# ESP32_with_USBC.net
KiCad netlist of a schematic drawn in Altium Designer
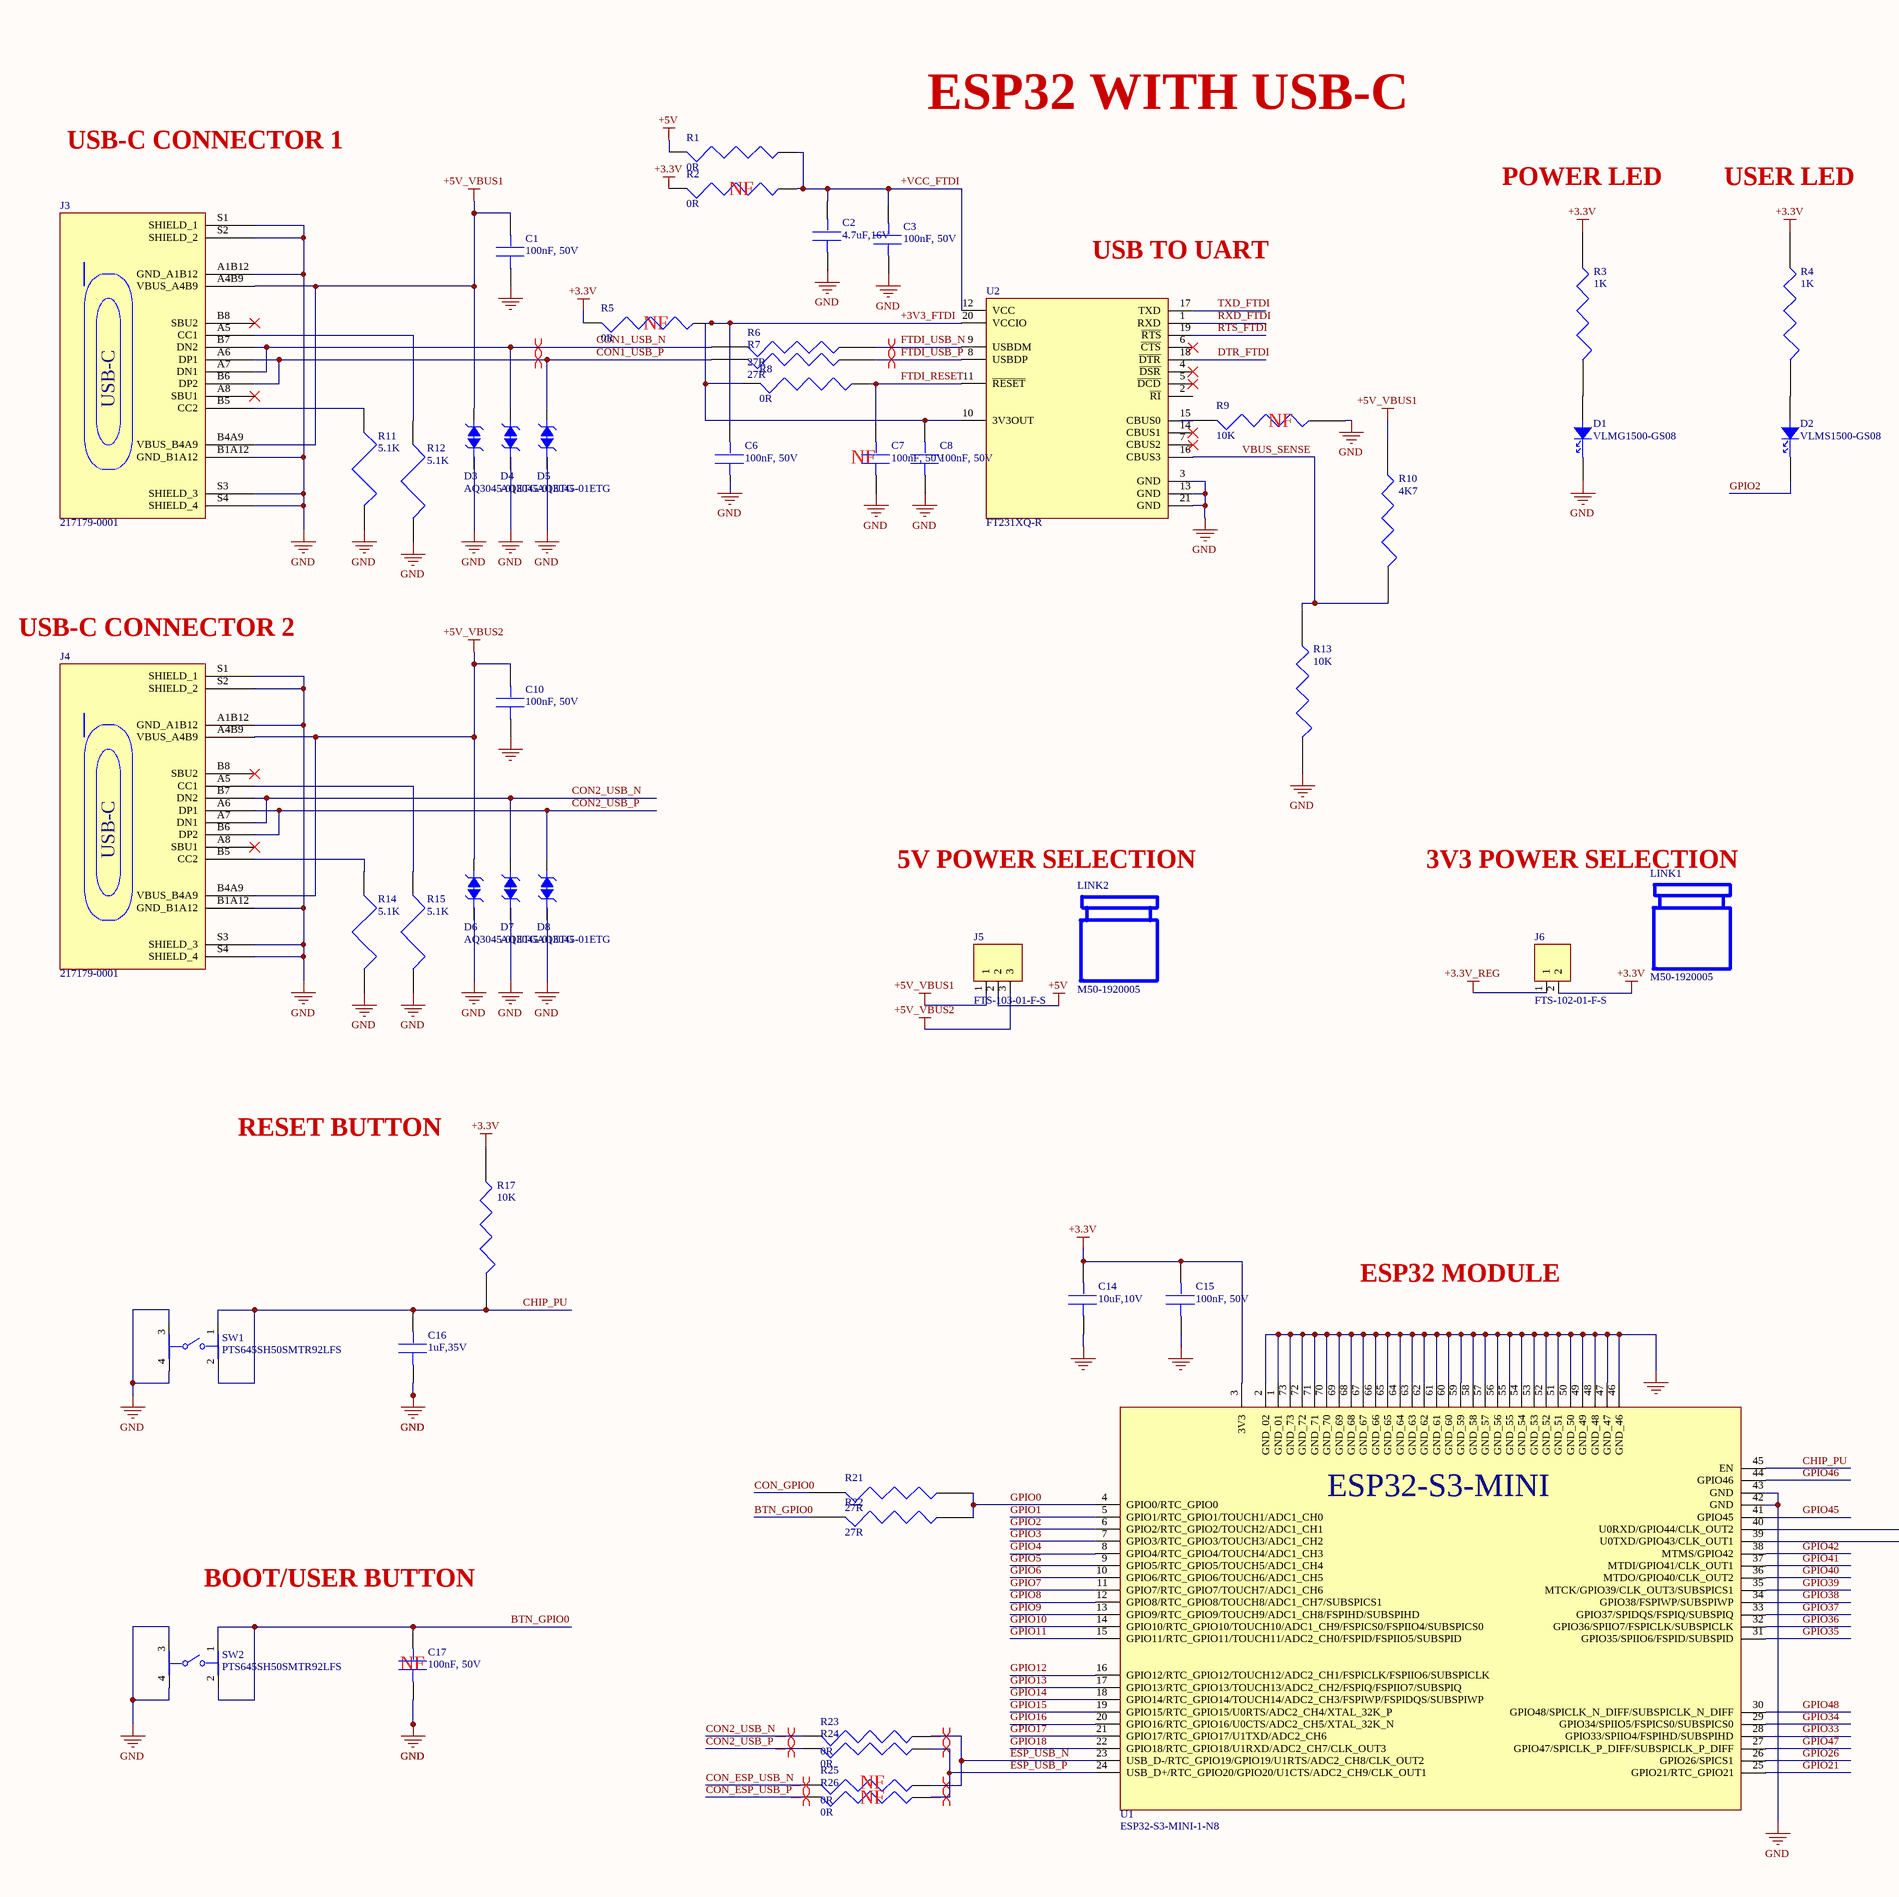
[diagram p0: ESP32 with USBC.SchDoc, left]
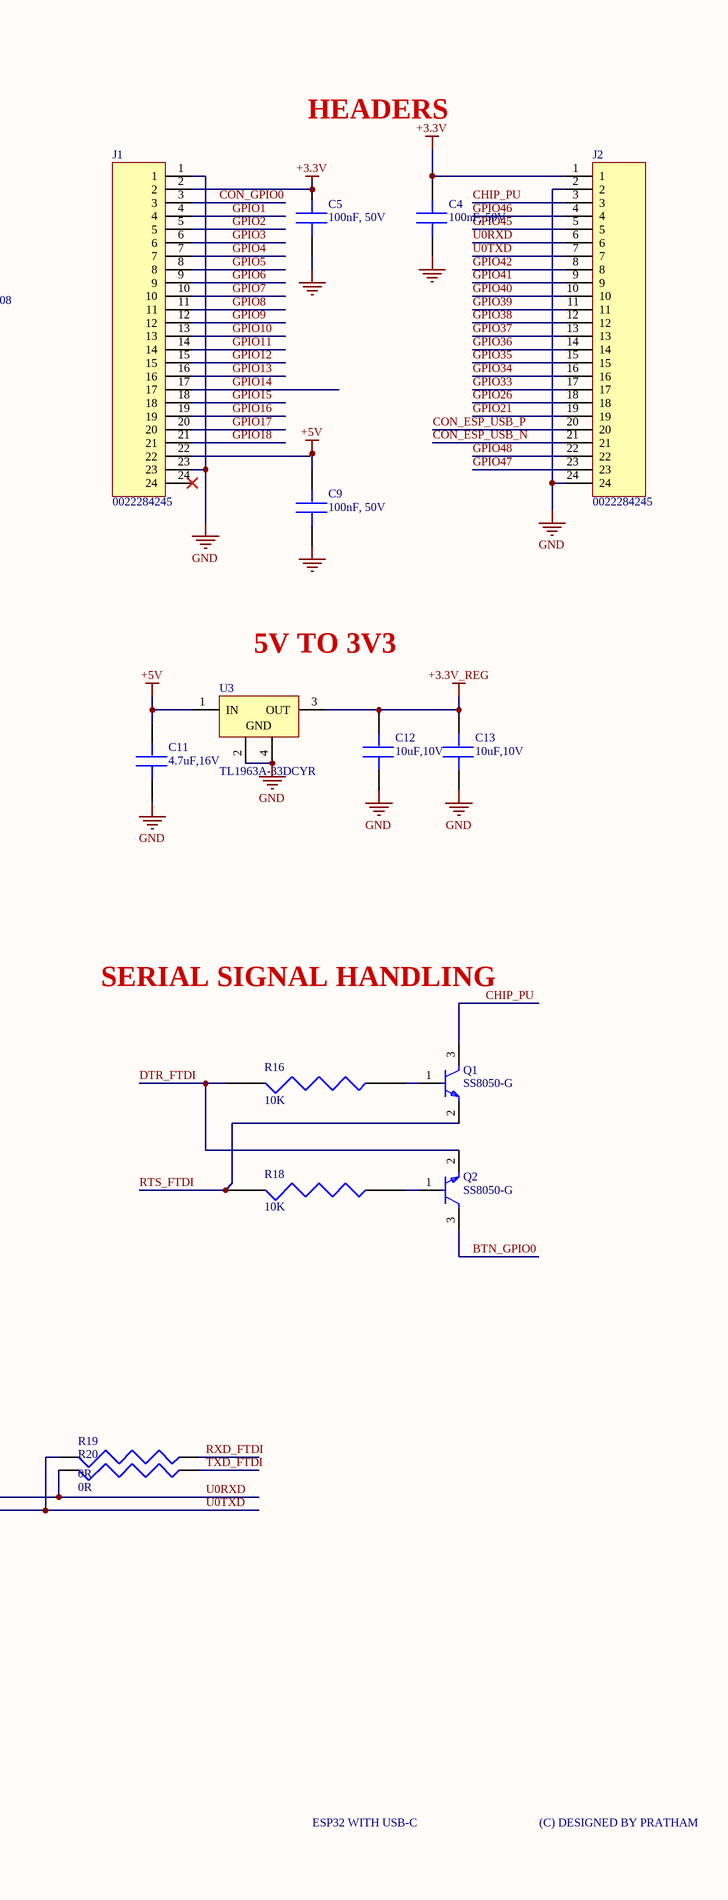
[diagram p1: ESP32 with USBC.SchDoc, right]

(export (version "E")
  (design (tool "Eeschema 10.0.6"))
  (components
    (comp (ref "C1")
      (value "100nF, 50V")
      (footprint "CAPC1005X55N")
      (description "CAP CER 0.1UF 50V X7R 0402")
      (fields (field (name "LCSC PART NUMBER") "C307331"))
      (libsource (lib "Schlib1") (part "CL05B104KB54PNC"))
    )
    (comp (ref "C2")
      (value "4.7uF,16V")
      (footprint "CAPC1005X55N")
      (description "CAP CER 4.7UF 16V X5R 0402")
      (fields
        (field (name "MANUFACTURER") "Samsung Electro-Mechanics")
        (field (name "MANUFACTURER PART NUMBER") "CL05A475MO5NUNC")
      )
      (libsource (lib "Schlib1") (part "CL05A475MO5NUNC"))
    )
    (comp (ref "C3")
      (value "100nF, 50V")
      (footprint "CAPC1005X55N")
      (description "CAP CER 0.1UF 50V X7R 0402")
      (fields (field (name "LCSC PART NUMBER") "C307331"))
      (libsource (lib "Schlib1") (part "CL05B104KB54PNC"))
    )
    (comp (ref "C4")
      (value "100nF, 50V")
      (footprint "CAPC1005X55N")
      (description "CAP CER 0.1UF 50V X7R 0402")
      (fields (field (name "LCSC PART NUMBER") "C307331"))
      (libsource (lib "Schlib1") (part "CL05B104KB54PNC"))
    )
    (comp (ref "C5")
      (value "100nF, 50V")
      (footprint "CAPC1005X55N")
      (description "CAP CER 0.1UF 50V X7R 0402")
      (fields (field (name "LCSC PART NUMBER") "C307331"))
      (libsource (lib "Schlib1") (part "CL05B104KB54PNC"))
    )
    (comp (ref "C6")
      (value "100nF, 50V")
      (footprint "CAPC1005X55N")
      (description "CAP CER 0.1UF 50V X7R 0402")
      (fields (field (name "LCSC PART NUMBER") "C307331"))
      (libsource (lib "Schlib1") (part "CL05B104KB54PNC"))
    )
    (comp (ref "C7")
      (value "100nF, 50V")
      (footprint "CAPC1005X55N")
      (description "CAP CER 0.1UF 50V X7R 0402")
      (fields (field (name "LCSC PART NUMBER") "C307331"))
      (libsource (lib "Schlib1") (part "CL05B104KB54PNC"))
    )
    (comp (ref "C8")
      (value "100nF, 50V")
      (footprint "CAPC1005X55N")
      (description "CAP CER 0.1UF 50V X7R 0402")
      (fields (field (name "LCSC PART NUMBER") "C307331"))
      (libsource (lib "Schlib1") (part "CL05B104KB54PNC"))
    )
    (comp (ref "C9")
      (value "100nF, 50V")
      (footprint "CAPC1005X55N")
      (description "CAP CER 0.1UF 50V X7R 0402")
      (fields (field (name "LCSC PART NUMBER") "C307331"))
      (libsource (lib "Schlib1") (part "CL05B104KB54PNC"))
    )
    (comp (ref "C10")
      (value "100nF, 50V")
      (footprint "CAPC1005X55N")
      (description "CAP CER 0.1UF 50V X7R 0402")
      (fields (field (name "LCSC PART NUMBER") "C307331"))
      (libsource (lib "Schlib1") (part "CL05B104KB54PNC"))
    )
    (comp (ref "C11")
      (value "4.7uF,16V")
      (footprint "CAPC1005X55N")
      (description "CAP CER 4.7UF 16V X5R 0402")
      (fields
        (field (name "MANUFACTURER") "Samsung Electro-Mechanics")
        (field (name "MANUFACTURER PART NUMBER") "CL05A475MO5NUNC")
      )
      (libsource (lib "Schlib1") (part "CL05A475MO5NUNC"))
    )
    (comp (ref "C12")
      (value "10uF,10V")
      (footprint "CAPC1005X55N")
      (description "CAP CER 10UF 10V X5R 0402")
      (fields
        (field (name "MANUFACTURER") "Samsung Electro-Mechanics")
        (field (name "MANUFACTURER PART NUMBER") "CL05A106MP8NUB8")
      )
      (libsource (lib "Schlib1") (part "CL05A106MP8NUB8"))
    )
    (comp (ref "C13")
      (value "10uF,10V")
      (footprint "CAPC1005X55N")
      (description "CAP CER 10UF 10V X5R 0402")
      (fields
        (field (name "MANUFACTURER") "Samsung Electro-Mechanics")
        (field (name "MANUFACTURER PART NUMBER") "CL05A106MP8NUB8")
      )
      (libsource (lib "Schlib1") (part "CL05A106MP8NUB8"))
    )
    (comp (ref "C14")
      (value "10uF,10V")
      (footprint "CAPC1005X55N")
      (description "CAP CER 10UF 10V X5R 0402")
      (fields
        (field (name "MANUFACTURER") "Samsung Electro-Mechanics")
        (field (name "MANUFACTURER PART NUMBER") "CL05A106MP8NUB8")
      )
      (libsource (lib "Schlib1") (part "CL05A106MP8NUB8"))
    )
    (comp (ref "C15")
      (value "100nF, 50V")
      (footprint "CAPC1005X55N")
      (description "CAP CER 0.1UF 50V X7R 0402")
      (fields (field (name "LCSC PART NUMBER") "C307331"))
      (libsource (lib "Schlib1") (part "CL05B104KB54PNC"))
    )
    (comp (ref "C16")
      (value "1uF,35V")
      (footprint "CAPC1005X55N")
      (description "CAP CER 1UF 35V X5R 0402")
      (fields
        (field (name "MANUFACTURER") "Samsung Electro-Mechanics")
        (field (name "MANUFACTURER PART NUMBER") "CL05A105KL5NRNC")
      )
      (libsource (lib "Schlib1") (part "CL05A105KL5NRNC"))
    )
    (comp (ref "C17")
      (value "100nF, 50V")
      (footprint "CAPC1005X55N")
      (description "CAP CER 0.1UF 50V X7R 0402")
      (fields (field (name "LCSC PART NUMBER") "C307331"))
      (libsource (lib "Schlib1") (part "CL05B104KB54PNC"))
    )
    (comp (ref "D1")
      (value "VLMG1500-GS08")
      (footprint "LED0402G")
      (description "LED YLW-GRN 0402 SMD")
      (fields (field (name "MANUFACTURER") "Vishay") (field (name "LCSC PART NUMBER") "C511404"))
      (libsource (lib "Schlib1") (part "VLMG1500-GS08"))
    )
    (comp (ref "D2")
      (value "VLMS1500-GS08")
      (footprint "LED0402R")
      (description "LED RED 0402 SMD")
      (fields (field (name "MANUFACTURER") "Vishay") (field (name "LCSC PART NUMBER") "C511370"))
      (libsource (lib "Schlib1") (part "VLMS1500-GS08"))
    )
    (comp (ref "D3")
      (value "AQ3045-01ETG")
      (footprint "S0D882")
      (description "TVS DIODE 5.3VWM 12VC SOD882")
      (fields (field (name "MANUFACTURER") "Littelfuse") (field (name "LCSC PART NUMBER") "C3710326"))
      (libsource (lib "Schlib1") (part "AQ3045-01ETG"))
    )
    (comp (ref "D4")
      (value "AQ3045-01ETG")
      (footprint "S0D882")
      (description "TVS DIODE 5.3VWM 12VC SOD882")
      (fields (field (name "MANUFACTURER") "Littelfuse") (field (name "LCSC PART NUMBER") "C3710326"))
      (libsource (lib "Schlib1") (part "AQ3045-01ETG"))
    )
    (comp (ref "D5")
      (value "AQ3045-01ETG")
      (footprint "S0D882")
      (description "TVS DIODE 5.3VWM 12VC SOD882")
      (fields (field (name "MANUFACTURER") "Littelfuse") (field (name "LCSC PART NUMBER") "C3710326"))
      (libsource (lib "Schlib1") (part "AQ3045-01ETG"))
    )
    (comp (ref "D6")
      (value "AQ3045-01ETG")
      (footprint "S0D882")
      (description "TVS DIODE 5.3VWM 12VC SOD882")
      (fields (field (name "MANUFACTURER") "Littelfuse") (field (name "LCSC PART NUMBER") "C3710326"))
      (libsource (lib "Schlib1") (part "AQ3045-01ETG"))
    )
    (comp (ref "D7")
      (value "AQ3045-01ETG")
      (footprint "S0D882")
      (description "TVS DIODE 5.3VWM 12VC SOD882")
      (fields (field (name "MANUFACTURER") "Littelfuse") (field (name "LCSC PART NUMBER") "C3710326"))
      (libsource (lib "Schlib1") (part "AQ3045-01ETG"))
    )
    (comp (ref "D8")
      (value "AQ3045-01ETG")
      (footprint "S0D882")
      (description "TVS DIODE 5.3VWM 12VC SOD882")
      (fields (field (name "MANUFACTURER") "Littelfuse") (field (name "LCSC PART NUMBER") "C3710326"))
      (libsource (lib "Schlib1") (part "AQ3045-01ETG"))
    )
    (comp (ref "J1")
      (value "0022284245")
      (footprint "HDR_1X24_2.54MM")
      (description "CONN HEADER VERT 24POS 2.54MM")
      (fields (field (name "MANUFACTURER") "Molex") (field (name "MANUFACTURER PART NUMBER") "22-28-4245"))
      (libsource (lib "Schlib1") (part "0022284245"))
    )
    (comp (ref "J2")
      (value "0022284245")
      (footprint "HDR_1X24_2.54MM")
      (description "CONN HEADER VERT 24POS 2.54MM")
      (fields (field (name "MANUFACTURER") "Molex") (field (name "MANUFACTURER PART NUMBER") "22-28-4245"))
      (libsource (lib "") (part "0022284245_1"))
    )
    (comp (ref "J3")
      (value "217179-0001")
      (footprint "FP-2171790001-MFG")
      (description "CONN RCP USB2.0 TYP C 24P SMD RA")
      (fields (field (name "MANUFACTURER") "Molex") (field (name "LCSC PART NUMBER") "C3197684"))
      (libsource (lib "Schlib1") (part "217179-0001"))
    )
    (comp (ref "J4")
      (value "217179-0001")
      (footprint "FP-2171790001-MFG")
      (description "CONN RCP USB2.0 TYP C 24P SMD RA")
      (fields (field (name "MANUFACTURER") "Molex") (field (name "LCSC PART NUMBER") "C3197684"))
      (libsource (lib "Schlib1") (part "217179-0001"))
    )
    (comp (ref "J5")
      (value "FTS-103-01-F-S")
      (footprint "HDR_1X3_27MM")
      (description "CONN HEADER VERT 3POS 1.27MM")
      (fields (field (name "MANUFACTURER") "Samtec") (field (name "LCSC PART NUMBER") "C3333578"))
      (libsource (lib "Schlib1") (part "FTS-103-01-F-S"))
    )
    (comp (ref "J6")
      (value "FTS-102-01-F-S")
      (footprint "HDR_1X2_1.27MM")
      (description "CONN HEADER VERT 2POS 1.27MM")
      (fields (field (name "MANUFACTURER") "Samtec") (field (name "LCSC PART NUMBER") "C6045317"))
      (libsource (lib "Schlib1") (part "FTS-102-01-F-S"))
    )
    (comp (ref "LINK1")
      (value "M50-1920005")
      (description "CONN SHUNT 1.27MM RED")
      (fields (field (name "MANUFACTURER") "Harwin") (field (name "LCSC PART NUMBER") "C6985646"))
      (libsource (lib "Schlib1") (part "M50-1920005"))
    )
    (comp (ref "LINK2")
      (value "M50-1920005")
      (description "CONN SHUNT 1.27MM RED")
      (fields (field (name "MANUFACTURER") "Harwin") (field (name "LCSC PART NUMBER") "C6985646"))
      (libsource (lib "Schlib1") (part "M50-1920005"))
    )
    (comp (ref "Q1")
      (value "SS8050-G")
      (footprint "FP-SS8050-G-IPC_B")
      (description "TRANS NPN 25V 1.5A SOT-23-3")
      (fields (field (name "MANUFACTURER") "Comchip") (field (name "LCSC PART NUMBER") "C3199946"))
      (libsource (lib "Schlib1") (part "SS8050-G"))
    )
    (comp (ref "Q2")
      (value "SS8050-G")
      (footprint "FP-SS8050-G-IPC_B")
      (description "TRANS NPN 25V 1.5A SOT-23-3")
      (fields (field (name "MANUFACTURER") "Comchip") (field (name "LCSC PART NUMBER") "C3199946"))
      (libsource (lib "Schlib1") (part "SS8050-G"))
    )
    (comp (ref "R1")
      (value "0R")
      (footprint "RESC1005X37N")
      (description "RES 0 OHM JUMPER 1/16W 0402")
      (fields
        (field (name "MANUFACTURER") "Yageo Group")
        (field (name "MANUFACTURER PART NUMBER") "RC0402JR-070RL")
      )
      (libsource (lib "Schlib1") (part "RC0402JR-070RL"))
    )
    (comp (ref "R2")
      (value "0R")
      (footprint "RESC1005X37N")
      (description "RES 0 OHM JUMPER 1/16W 0402")
      (fields
        (field (name "MANUFACTURER") "Yageo Group")
        (field (name "MANUFACTURER PART NUMBER") "RC0402JR-070RL")
      )
      (libsource (lib "Schlib1") (part "RC0402JR-070RL"))
    )
    (comp (ref "R3")
      (value "1K")
      (footprint "RESC1005X37N")
      (description "RES 1K OHM 1% 1/16W 0402")
      (fields
        (field (name "MANUFACTURER") "Yageo Group")
        (field (name "MANUFACTURER PART NUMBER") "RC0402FR-071KL")
      )
      (libsource (lib "Schlib1") (part "RC0402FR-071KL"))
    )
    (comp (ref "R4")
      (value "1K")
      (footprint "RESC1005X37N")
      (description "RES 1K OHM 1% 1/16W 0402")
      (fields
        (field (name "MANUFACTURER") "Yageo Group")
        (field (name "MANUFACTURER PART NUMBER") "RC0402FR-071KL")
      )
      (libsource (lib "Schlib1") (part "RC0402FR-071KL"))
    )
    (comp (ref "R5")
      (value "0R")
      (footprint "RESC1005X37N")
      (description "RES 0 OHM JUMPER 1/16W 0402")
      (fields
        (field (name "MANUFACTURER") "Yageo Group")
        (field (name "MANUFACTURER PART NUMBER") "RC0402JR-070RL")
      )
      (libsource (lib "Schlib1") (part "RC0402JR-070RL"))
    )
    (comp (ref "R6")
      (value "27R")
      (footprint "RESC1005X37N")
      (description "RES 27 OHM 1% 1/16W 0402")
      (fields
        (field (name "MANUFACTURER") "Yageo Group")
        (field (name "MANUFACTURER PART NUMBER") "RC0402FR-0727RL")
      )
      (libsource (lib "Schlib1") (part "RC0402FR-0727RL"))
    )
    (comp (ref "R7")
      (value "27R")
      (footprint "RESC1005X37N")
      (description "RES 27 OHM 1% 1/16W 0402")
      (fields
        (field (name "MANUFACTURER") "Yageo Group")
        (field (name "MANUFACTURER PART NUMBER") "RC0402FR-0727RL")
      )
      (libsource (lib "Schlib1") (part "RC0402FR-0727RL"))
    )
    (comp (ref "R8")
      (value "0R")
      (footprint "RESC1005X37N")
      (description "RES 0 OHM JUMPER 1/16W 0402")
      (fields
        (field (name "MANUFACTURER") "Yageo Group")
        (field (name "MANUFACTURER PART NUMBER") "RC0402JR-070RL")
      )
      (libsource (lib "Schlib1") (part "RC0402JR-070RL"))
    )
    (comp (ref "R9")
      (value "10K")
      (footprint "RESC1005X37N")
      (description "RES SMD 10K OHM 1% 1/16W 0402")
      (fields
        (field (name "MANUFACTURER") "Yageo Group")
        (field (name "MANUFACTURER PART NUMBER") "AC0402FR-0710KL")
      )
      (libsource (lib "Schlib1") (part "AC0402FR-0710KL"))
    )
    (comp (ref "R10")
      (value "4K7")
      (footprint "RESC1005X37N")
      (description "RES 4.7K OHM 1% 1/16W 0402")
      (fields
        (field (name "MANUFACTURER") "Yageo Group")
        (field (name "MANUFACTURER PART NUMBER") "RC0402FR-074K7L")
      )
      (libsource (lib "Schlib1") (part "RC0402FR-074K7L"))
    )
    (comp (ref "R11")
      (value "5.1K")
      (footprint "RESC1005X37N")
      (description "RES 5.1K OHM 1% 1/8W 0402")
      (fields
        (field (name "MANUFACTURER") "Yageo Group")
        (field (name "MANUFACTURER PART NUMBER") "AC0402FR-7W5K1L")
      )
      (libsource (lib "Schlib1") (part "AC0402FR-7W5K1L"))
    )
    (comp (ref "R12")
      (value "5.1K")
      (footprint "RESC1005X37N")
      (description "RES 5.1K OHM 1% 1/8W 0402")
      (fields
        (field (name "MANUFACTURER") "Yageo Group")
        (field (name "MANUFACTURER PART NUMBER") "AC0402FR-7W5K1L")
      )
      (libsource (lib "Schlib1") (part "AC0402FR-7W5K1L"))
    )
    (comp (ref "R13")
      (value "10K")
      (footprint "RESC1005X37N")
      (description "RES SMD 10K OHM 1% 1/16W 0402")
      (fields
        (field (name "MANUFACTURER") "Yageo Group")
        (field (name "MANUFACTURER PART NUMBER") "AC0402FR-0710KL")
      )
      (libsource (lib "Schlib1") (part "AC0402FR-0710KL"))
    )
    (comp (ref "R14")
      (value "5.1K")
      (footprint "RESC1005X37N")
      (description "RES 5.1K OHM 1% 1/8W 0402")
      (fields
        (field (name "MANUFACTURER") "Yageo Group")
        (field (name "MANUFACTURER PART NUMBER") "AC0402FR-7W5K1L")
      )
      (libsource (lib "Schlib1") (part "AC0402FR-7W5K1L"))
    )
    (comp (ref "R15")
      (value "5.1K")
      (footprint "RESC1005X37N")
      (description "RES 5.1K OHM 1% 1/8W 0402")
      (fields
        (field (name "MANUFACTURER") "Yageo Group")
        (field (name "MANUFACTURER PART NUMBER") "AC0402FR-7W5K1L")
      )
      (libsource (lib "Schlib1") (part "AC0402FR-7W5K1L"))
    )
    (comp (ref "R16")
      (value "10K")
      (footprint "RESC1005X37N")
      (description "RES SMD 10K OHM 1% 1/16W 0402")
      (fields
        (field (name "MANUFACTURER") "Yageo Group")
        (field (name "MANUFACTURER PART NUMBER") "AC0402FR-0710KL")
      )
      (libsource (lib "Schlib1") (part "AC0402FR-0710KL"))
    )
    (comp (ref "R17")
      (value "10K")
      (footprint "RESC1005X37N")
      (description "RES SMD 10K OHM 1% 1/16W 0402")
      (fields
        (field (name "MANUFACTURER") "Yageo Group")
        (field (name "MANUFACTURER PART NUMBER") "AC0402FR-0710KL")
      )
      (libsource (lib "") (part "AC0402FR-0710KL_1"))
    )
    (comp (ref "R18")
      (value "10K")
      (footprint "RESC1005X37N")
      (description "RES SMD 10K OHM 1% 1/16W 0402")
      (fields
        (field (name "MANUFACTURER") "Yageo Group")
        (field (name "MANUFACTURER PART NUMBER") "AC0402FR-0710KL")
      )
      (libsource (lib "") (part "AC0402FR-0710KL_1"))
    )
    (comp (ref "R19")
      (value "0R")
      (footprint "RESC1005X37N")
      (description "RES 0 OHM JUMPER 1/16W 0402")
      (fields
        (field (name "MANUFACTURER") "Yageo Group")
        (field (name "MANUFACTURER PART NUMBER") "RC0402JR-070RL")
      )
      (libsource (lib "Schlib1") (part "RC0402JR-070RL"))
    )
    (comp (ref "R20")
      (value "0R")
      (footprint "RESC1005X37N")
      (description "RES 0 OHM JUMPER 1/16W 0402")
      (fields
        (field (name "MANUFACTURER") "Yageo Group")
        (field (name "MANUFACTURER PART NUMBER") "RC0402JR-070RL")
      )
      (libsource (lib "Schlib1") (part "RC0402JR-070RL"))
    )
    (comp (ref "R21")
      (value "27R")
      (footprint "RESC1005X37N")
      (description "RES 27 OHM 1% 1/16W 0402")
      (fields
        (field (name "MANUFACTURER") "Yageo Group")
        (field (name "MANUFACTURER PART NUMBER") "RC0402FR-0727RL")
      )
      (libsource (lib "Schlib1") (part "RC0402FR-0727RL"))
    )
    (comp (ref "R22")
      (value "27R")
      (footprint "RESC1005X37N")
      (description "RES 27 OHM 1% 1/16W 0402")
      (fields
        (field (name "MANUFACTURER") "Yageo Group")
        (field (name "MANUFACTURER PART NUMBER") "RC0402FR-0727RL")
      )
      (libsource (lib "Schlib1") (part "RC0402FR-0727RL"))
    )
    (comp (ref "R23")
      (value "0R")
      (footprint "RESC1005X37N")
      (description "RES 0 OHM JUMPER 1/16W 0402")
      (fields
        (field (name "MANUFACTURER") "Yageo Group")
        (field (name "MANUFACTURER PART NUMBER") "RC0402JR-070RL")
      )
      (libsource (lib "Schlib1") (part "RC0402JR-070RL"))
    )
    (comp (ref "R24")
      (value "0R")
      (footprint "RESC1005X37N")
      (description "RES 0 OHM JUMPER 1/16W 0402")
      (fields
        (field (name "MANUFACTURER") "Yageo Group")
        (field (name "MANUFACTURER PART NUMBER") "RC0402JR-070RL")
      )
      (libsource (lib "Schlib1") (part "RC0402JR-070RL"))
    )
    (comp (ref "R25")
      (value "0R")
      (footprint "RESC1005X37N")
      (description "RES 0 OHM JUMPER 1/16W 0402")
      (fields
        (field (name "MANUFACTURER") "Yageo Group")
        (field (name "MANUFACTURER PART NUMBER") "RC0402JR-070RL")
      )
      (libsource (lib "Schlib1") (part "RC0402JR-070RL"))
    )
    (comp (ref "R26")
      (value "0R")
      (footprint "RESC1005X37N")
      (description "RES 0 OHM JUMPER 1/16W 0402")
      (fields
        (field (name "MANUFACTURER") "Yageo Group")
        (field (name "MANUFACTURER PART NUMBER") "RC0402JR-070RL")
      )
      (libsource (lib "Schlib1") (part "RC0402JR-070RL"))
    )
    (comp (ref "SW1")
      (value "PTS645SH50SMTR92LFS")
      (footprint "FP-PTS645SH50SMTR92LFS-MFG")
      (description "SWITCH TACTILE SPST-NO 0.05A 12V")
      (fields (field (name "MANUFACTURER") "C&K Components") (field (name "LCSC PART NUMBER") "C221869"))
      (libsource (lib "Schlib1") (part "PTS645SH50SMTR92LFS"))
    )
    (comp (ref "SW2")
      (value "PTS645SH50SMTR92LFS")
      (footprint "FP-PTS645SH50SMTR92LFS-MFG")
      (description "SWITCH TACTILE SPST-NO 0.05A 12V")
      (fields (field (name "MANUFACTURER") "C&K Components") (field (name "LCSC PART NUMBER") "C221869"))
      (libsource (lib "Schlib1") (part "PTS645SH50SMTR92LFS"))
    )
    (comp (ref "U1")
      (value "ESP32-S3-MINI-1-N8")
      (footprint "XCVR_ESP32-S3-MINI-1-N8")
      (description "SMD module, ESP32-S3FN8, 8 MB SPI flash, PCB antenna")
      (fields (field (name "MANUFACTURER") "Espressif Systems") (field (name "LCSCPART NUMBER") "C2913206"))
      (libsource (lib "Schlib1") (part "ESP32-S3-MINI-1-N8"))
    )
    (comp (ref "U2")
      (value "FT231XQ-R")
      (footprint "FP-QFN-20-IPC_B")
      (description "IC USB SERIAL FULL UART 20QFN")
      (fields (field (name "MANUFACTURER") "FTDI") (field (name "LCSC PART NUMBER") "C132159"))
      (libsource (lib "Schlib1") (part "FT231XQ-R"))
    )
    (comp (ref "U3")
      (value "TL1963A-33DCYR")
      (footprint "DCY0004A_N")
      (description "IC REG LIN 3.3V 1.5A SOT-223-4")
      (fields (field (name "MANUFACTURER") "Texas Instruments") (field (name "LCSC PART NUMBER") "C181262"))
      (libsource (lib "Schlib1") (part "TL1963A-33DCYR"))
    )
  )
  (nets
    (net (code "1") (name "+3.3V") (class "Default")
      (node (ref "C14") (pin "2") (pinfunction "1_2") (pintype "passive"))
      (node (ref "C15") (pin "2") (pinfunction "2_2") (pintype "passive"))
      (node (ref "C4") (pin "2") (pinfunction "2_2") (pintype "passive"))
      (node (ref "C5") (pin "2") (pinfunction "2_2") (pintype "passive"))
      (node (ref "J1") (pin "2") (pinfunction "2_2") (pintype "passive"))
      (node (ref "J2") (pin "1") (pinfunction "1_1") (pintype "passive"))
      (node (ref "J6") (pin "2") (pinfunction "2_2") (pintype "passive"))
      (node (ref "R17") (pin "2") (pinfunction "2_2") (pintype "passive"))
      (node (ref "R2") (pin "1") (pinfunction "1_1") (pintype "passive"))
      (node (ref "R3") (pin "2") (pinfunction "2_2") (pintype "passive"))
      (node (ref "R4") (pin "2") (pinfunction "2_2") (pintype "passive"))
      (node (ref "R5") (pin "1") (pinfunction "1_1") (pintype "passive"))
      (node (ref "U1") (pin "3") (pinfunction "3V3_3") (pintype "passive"))
    )
    (net (code "2") (name "+3.3V_REG") (class "Default")
      (node (ref "C12") (pin "2") (pinfunction "1_2") (pintype "passive"))
      (node (ref "C13") (pin "2") (pinfunction "1_2") (pintype "passive"))
      (node (ref "J6") (pin "1") (pinfunction "1_1") (pintype "passive"))
      (node (ref "U3") (pin "3") (pinfunction "OUT_3") (pintype "power_in"))
    )
    (net (code "3") (name "+5V") (class "Default")
      (node (ref "C11") (pin "2") (pinfunction "1_2") (pintype "passive"))
      (node (ref "C9") (pin "2") (pinfunction "2_2") (pintype "passive"))
      (node (ref "J1") (pin "22") (pinfunction "22_22") (pintype "passive"))
      (node (ref "J5") (pin "2") (pinfunction "2_2") (pintype "passive"))
      (node (ref "R1") (pin "1") (pinfunction "1_1") (pintype "passive"))
      (node (ref "U3") (pin "1") (pinfunction "IN_1") (pintype "power_in"))
    )
    (net (code "4") (name "+5V_VBUS1") (class "Default")
      (node (ref "C1") (pin "2") (pinfunction "2_2") (pintype "passive"))
      (node (ref "D3") (pin "2") (pinfunction "2_2") (pintype "passive"))
      (node (ref "J3") (pin "A4B9") (pinfunction "VBUS_A4B9_A4B9") (pintype "passive"))
      (node (ref "J3") (pin "B4A9") (pinfunction "VBUS_B4A9_B4A9") (pintype "passive"))
      (node (ref "J5") (pin "1") (pinfunction "1_1") (pintype "passive"))
      (node (ref "R10") (pin "1") (pinfunction "1_1") (pintype "passive"))
    )
    (net (code "5") (name "+5V_VBUS2") (class "Default")
      (node (ref "C10") (pin "2") (pinfunction "2_2") (pintype "passive"))
      (node (ref "D6") (pin "2") (pinfunction "2_2") (pintype "passive"))
      (node (ref "J4") (pin "A4B9") (pinfunction "VBUS_A4B9_A4B9") (pintype "passive"))
      (node (ref "J4") (pin "B4A9") (pinfunction "VBUS_B4A9_B4A9") (pintype "passive"))
      (node (ref "J5") (pin "3") (pinfunction "3_3") (pintype "passive"))
    )
    (net (code "6") (name "/+3V3_FTDI") (class "Default")
      (node (ref "C6") (pin "2") (pinfunction "2_2") (pintype "passive"))
      (node (ref "C8") (pin "2") (pinfunction "2_2") (pintype "passive"))
      (node (ref "R5") (pin "2") (pinfunction "2_2") (pintype "passive"))
      (node (ref "R8") (pin "1") (pinfunction "1_1") (pintype "passive"))
      (node (ref "U2") (pin "10") (pinfunction "3V3OUT_10") (pintype "passive"))
      (node (ref "U2") (pin "20") (pinfunction "VCCIO_20") (pintype "passive"))
    )
    (net (code "7") (name "/+VCC_FTDI") (class "Default")
      (node (ref "C2") (pin "2") (pinfunction "1_2") (pintype "passive"))
      (node (ref "C3") (pin "2") (pinfunction "2_2") (pintype "passive"))
      (node (ref "R1") (pin "2") (pinfunction "2_2") (pintype "passive"))
      (node (ref "R2") (pin "2") (pinfunction "2_2") (pintype "passive"))
      (node (ref "U2") (pin "12") (pinfunction "VCC_12") (pintype "passive"))
    )
    (net (code "8") (name "/BTN_GPIO0") (class "Default")
      (node (ref "C17") (pin "2") (pinfunction "2_2") (pintype "passive"))
      (node (ref "Q2") (pin "3") (pinfunction "C_3") (pintype "passive"))
      (node (ref "R22") (pin "1") (pinfunction "1_1") (pintype "passive"))
      (node (ref "SW2") (pin "1") (pinfunction "1_1") (pintype "passive"))
      (node (ref "SW2") (pin "2") (pinfunction "2_2") (pintype "passive"))
    )
    (net (code "9") (name "/CHIP_PU") (class "Default")
      (node (ref "C16") (pin "2") (pinfunction "1_2") (pintype "passive"))
      (node (ref "J2") (pin "3") (pinfunction "3_3") (pintype "passive"))
      (node (ref "Q1") (pin "3") (pinfunction "C_3") (pintype "passive"))
      (node (ref "R17") (pin "1") (pinfunction "1_1") (pintype "passive"))
      (node (ref "SW1") (pin "1") (pinfunction "1_1") (pintype "passive"))
      (node (ref "SW1") (pin "2") (pinfunction "2_2") (pintype "passive"))
      (node (ref "U1") (pin "45") (pinfunction "EN_45") (pintype "passive"))
    )
    (net (code "10") (name "/CON1_USB_N") (class "Default")
      (node (ref "D4") (pin "2") (pinfunction "2_2") (pintype "passive"))
      (node (ref "J3") (pin "A7") (pinfunction "DN1_A7") (pintype "passive"))
      (node (ref "J3") (pin "B7") (pinfunction "DN2_B7") (pintype "passive"))
      (node (ref "R6") (pin "1") (pinfunction "1_1") (pintype "passive"))
    )
    (net (code "11") (name "/CON1_USB_P") (class "Default")
      (node (ref "D5") (pin "2") (pinfunction "2_2") (pintype "passive"))
      (node (ref "J3") (pin "A6") (pinfunction "DP1_A6") (pintype "passive"))
      (node (ref "J3") (pin "B6") (pinfunction "DP2_B6") (pintype "passive"))
      (node (ref "R7") (pin "1") (pinfunction "1_1") (pintype "passive"))
    )
    (net (code "12") (name "/CON2_USB_N") (class "Default")
      (node (ref "D7") (pin "2") (pinfunction "2_2") (pintype "passive"))
      (node (ref "J4") (pin "A7") (pinfunction "DN1_A7") (pintype "passive"))
      (node (ref "J4") (pin "B7") (pinfunction "DN2_B7") (pintype "passive"))
      (node (ref "R23") (pin "1") (pinfunction "1_1") (pintype "passive"))
    )
    (net (code "13") (name "/CON2_USB_P") (class "Default")
      (node (ref "D8") (pin "2") (pinfunction "2_2") (pintype "passive"))
      (node (ref "J4") (pin "A6") (pinfunction "DP1_A6") (pintype "passive"))
      (node (ref "J4") (pin "B6") (pinfunction "DP2_B6") (pintype "passive"))
      (node (ref "R24") (pin "1") (pinfunction "1_1") (pintype "passive"))
    )
    (net (code "14") (name "/CON_ESP_USB_N") (class "Default")
      (node (ref "J2") (pin "21") (pinfunction "21_21") (pintype "passive"))
      (node (ref "R25") (pin "1") (pinfunction "1_1") (pintype "passive"))
    )
    (net (code "15") (name "/CON_ESP_USB_P") (class "Default")
      (node (ref "J2") (pin "20") (pinfunction "20_20") (pintype "passive"))
      (node (ref "R26") (pin "1") (pinfunction "1_1") (pintype "passive"))
    )
    (net (code "16") (name "/CON_GPIO0") (class "Default")
      (node (ref "J1") (pin "3") (pinfunction "3_3") (pintype "passive"))
      (node (ref "R21") (pin "1") (pinfunction "1_1") (pintype "passive"))
    )
    (net (code "17") (name "/DTR_FTDI") (class "Default")
      (node (ref "Q2") (pin "2") (pinfunction "E_2") (pintype "passive"))
      (node (ref "R16") (pin "2") (pinfunction "2_2") (pintype "passive"))
      (node (ref "U2") (pin "18") (pinfunction "~{DTR}_18") (pintype "passive"))
    )
    (net (code "18") (name "/ESP_USB_N") (class "Default")
      (node (ref "R23") (pin "2") (pinfunction "2_2") (pintype "passive"))
      (node (ref "R25") (pin "2") (pinfunction "2_2") (pintype "passive"))
      (node (ref "U1") (pin "23") (pinfunction "USB_D-/RTC_GPIO19/GPIO19/U1RTS/ADC2_CH8/CLK_OUT2_23") (pintype "passive"))
    )
    (net (code "19") (name "/ESP_USB_P") (class "Default")
      (node (ref "R24") (pin "2") (pinfunction "2_2") (pintype "passive"))
      (node (ref "R26") (pin "2") (pinfunction "2_2") (pintype "passive"))
      (node (ref "U1") (pin "24") (pinfunction "USB_D+/RTC_GPIO20/GPIO20/U1CTS/ADC2_CH9/CLK_OUT1_24") (pintype "passive"))
    )
    (net (code "20") (name "/FTDI_RESET") (class "Default")
      (node (ref "C7") (pin "2") (pinfunction "2_2") (pintype "passive"))
      (node (ref "R8") (pin "2") (pinfunction "2_2") (pintype "passive"))
      (node (ref "U2") (pin "11") (pinfunction "~{RESET}_11") (pintype "passive"))
    )
    (net (code "21") (name "/FTDI_USB_N") (class "Default")
      (node (ref "R6") (pin "2") (pinfunction "2_2") (pintype "passive"))
      (node (ref "U2") (pin "9") (pinfunction "USBDM_9") (pintype "passive"))
    )
    (net (code "22") (name "/FTDI_USB_P") (class "Default")
      (node (ref "R7") (pin "2") (pinfunction "2_2") (pintype "passive"))
      (node (ref "U2") (pin "8") (pinfunction "USBDP_8") (pintype "passive"))
    )
    (net (code "23") (name "/GPIO0") (class "Default")
      (node (ref "R21") (pin "2") (pinfunction "2_2") (pintype "passive"))
      (node (ref "R22") (pin "2") (pinfunction "2_2") (pintype "passive"))
      (node (ref "U1") (pin "4") (pinfunction "GPIO0/RTC_GPIO0_4") (pintype "passive"))
    )
    (net (code "24") (name "/GPIO1") (class "Default")
      (node (ref "J1") (pin "4") (pinfunction "4_4") (pintype "passive"))
      (node (ref "U1") (pin "5") (pinfunction "GPIO1/RTC_GPIO1/TOUCH1/ADC1_CH0_5") (pintype "passive"))
    )
    (net (code "25") (name "/GPIO2") (class "Default")
      (node (ref "D2") (pin "1") (pinfunction "1_1") (pintype "passive"))
      (node (ref "J1") (pin "5") (pinfunction "5_5") (pintype "passive"))
      (node (ref "U1") (pin "6") (pinfunction "GPIO2/RTC_GPIO2/TOUCH2/ADC1_CH1_6") (pintype "passive"))
    )
    (net (code "26") (name "/GPIO3") (class "Default")
      (node (ref "J1") (pin "6") (pinfunction "6_6") (pintype "passive"))
      (node (ref "U1") (pin "7") (pinfunction "GPIO3/RTC_GPIO3/TOUCH3/ADC1_CH2_7") (pintype "passive"))
    )
    (net (code "27") (name "/GPIO4") (class "Default")
      (node (ref "J1") (pin "7") (pinfunction "7_7") (pintype "passive"))
      (node (ref "U1") (pin "8") (pinfunction "GPIO4/RTC_GPIO4/TOUCH4/ADC1_CH3_8") (pintype "passive"))
    )
    (net (code "28") (name "/GPIO5") (class "Default")
      (node (ref "J1") (pin "8") (pinfunction "8_8") (pintype "passive"))
      (node (ref "U1") (pin "9") (pinfunction "GPIO5/RTC_GPIO5/TOUCH5/ADC1_CH4_9") (pintype "passive"))
    )
    (net (code "29") (name "/GPIO6") (class "Default")
      (node (ref "J1") (pin "9") (pinfunction "9_9") (pintype "passive"))
      (node (ref "U1") (pin "10") (pinfunction "GPIO6/RTC_GPIO6/TOUCH6/ADC1_CH5_10") (pintype "passive"))
    )
    (net (code "30") (name "/GPIO7") (class "Default")
      (node (ref "J1") (pin "10") (pinfunction "10_10") (pintype "passive"))
      (node (ref "U1") (pin "11") (pinfunction "GPIO7/RTC_GPIO7/TOUCH7/ADC1_CH6_11") (pintype "passive"))
    )
    (net (code "31") (name "/GPIO8") (class "Default")
      (node (ref "J1") (pin "11") (pinfunction "11_11") (pintype "passive"))
      (node (ref "U1") (pin "12") (pinfunction "GPIO8/RTC_GPIO8/TOUCH8/ADC1_CH7/SUBSPICS1_12") (pintype "passive"))
    )
    (net (code "32") (name "/GPIO9") (class "Default")
      (node (ref "J1") (pin "12") (pinfunction "12_12") (pintype "passive"))
      (node (ref "U1") (pin "13") (pinfunction "GPIO9/RTC_GPIO9/TOUCH9/ADC1_CH8/FSPIHD/SUBSPIHD_13") (pintype "passive"))
    )
    (net (code "33") (name "/GPIO10") (class "Default")
      (node (ref "J1") (pin "13") (pinfunction "13_13") (pintype "passive"))
      (node (ref "U1") (pin "14") (pinfunction "GPIO10/RTC_GPIO10/TOUCH10/ADC1_CH9/FSPICS0/FSPIIO4/SUBSPICS0_14") (pintype "passive"))
    )
    (net (code "34") (name "/GPIO11") (class "Default")
      (node (ref "J1") (pin "14") (pinfunction "14_14") (pintype "passive"))
      (node (ref "U1") (pin "15") (pinfunction "GPIO11/RTC_GPIO11/TOUCH11/ADC2_CH0/FSPID/FSPIIO5/SUBSPID_15") (pintype "passive"))
    )
    (net (code "35") (name "/GPIO12") (class "Default")
      (node (ref "J1") (pin "15") (pinfunction "15_15") (pintype "passive"))
      (node (ref "U1") (pin "16") (pinfunction "GPIO12/RTC_GPIO12/TOUCH12/ADC2_CH1/FSPICLK/FSPIIO6/SUBSPICLK_16") (pintype "passive"))
    )
    (net (code "36") (name "/GPIO13") (class "Default")
      (node (ref "J1") (pin "16") (pinfunction "16_16") (pintype "passive"))
      (node (ref "U1") (pin "17") (pinfunction "GPIO13/RTC_GPIO13/TOUCH13/ADC2_CH2/FSPIQ/FSPIIO7/SUBSPIQ_17") (pintype "passive"))
    )
    (net (code "37") (name "/GPIO14") (class "Default")
      (node (ref "J1") (pin "17") (pinfunction "17_17") (pintype "passive"))
      (node (ref "U1") (pin "18") (pinfunction "GPIO14/RTC_GPIO14/TOUCH14/ADC2_CH3/FSPIWP/FSPIDQS/SUBSPIWP_18") (pintype "passive"))
    )
    (net (code "38") (name "/GPIO15") (class "Default")
      (node (ref "J1") (pin "18") (pinfunction "18_18") (pintype "passive"))
      (node (ref "U1") (pin "19") (pinfunction "GPIO15/RTC_GPIO15/U0RTS/ADC2_CH4/XTAL_32K_P_19") (pintype "passive"))
    )
    (net (code "39") (name "/GPIO16") (class "Default")
      (node (ref "J1") (pin "19") (pinfunction "19_19") (pintype "passive"))
      (node (ref "U1") (pin "20") (pinfunction "GPIO16/RTC_GPIO16/U0CTS/ADC2_CH5/XTAL_32K_N_20") (pintype "passive"))
    )
    (net (code "40") (name "/GPIO17") (class "Default")
      (node (ref "J1") (pin "20") (pinfunction "20_20") (pintype "passive"))
      (node (ref "U1") (pin "21") (pinfunction "GPIO17/RTC_GPIO17/U1TXD/ADC2_CH6_21") (pintype "passive"))
    )
    (net (code "41") (name "/GPIO18") (class "Default")
      (node (ref "J1") (pin "21") (pinfunction "21_21") (pintype "passive"))
      (node (ref "U1") (pin "22") (pinfunction "GPIO18/RTC_GPIO18/U1RXD/ADC2_CH7/CLK_OUT3_22") (pintype "passive"))
    )
    (net (code "42") (name "/GPIO21") (class "Default")
      (node (ref "J2") (pin "19") (pinfunction "19_19") (pintype "passive"))
      (node (ref "U1") (pin "25") (pinfunction "GPIO21/RTC_GPIO21_25") (pintype "passive"))
    )
    (net (code "43") (name "/GPIO26") (class "Default")
      (node (ref "J2") (pin "18") (pinfunction "18_18") (pintype "passive"))
      (node (ref "U1") (pin "26") (pinfunction "GPIO26/SPICS1_26") (pintype "passive"))
    )
    (net (code "44") (name "/GPIO33") (class "Default")
      (node (ref "J2") (pin "17") (pinfunction "17_17") (pintype "passive"))
      (node (ref "U1") (pin "28") (pinfunction "GPIO33/SPIIO4/FSPIHD/SUBSPIHD_28") (pintype "passive"))
    )
    (net (code "45") (name "/GPIO34") (class "Default")
      (node (ref "J2") (pin "16") (pinfunction "16_16") (pintype "passive"))
      (node (ref "U1") (pin "29") (pinfunction "GPIO34/SPIIO5/FSPICS0/SUBSPICS0_29") (pintype "passive"))
    )
    (net (code "46") (name "/GPIO35") (class "Default")
      (node (ref "J2") (pin "15") (pinfunction "15_15") (pintype "passive"))
      (node (ref "U1") (pin "31") (pinfunction "GPIO35/SPIIO6/FSPID/SUBSPID_31") (pintype "passive"))
    )
    (net (code "47") (name "/GPIO36") (class "Default")
      (node (ref "J2") (pin "14") (pinfunction "14_14") (pintype "passive"))
      (node (ref "U1") (pin "32") (pinfunction "GPIO36/SPIIO7/FSPICLK/SUBSPICLK_32") (pintype "passive"))
    )
    (net (code "48") (name "/GPIO37") (class "Default")
      (node (ref "J2") (pin "13") (pinfunction "13_13") (pintype "passive"))
      (node (ref "U1") (pin "33") (pinfunction "GPIO37/SPIDQS/FSPIQ/SUBSPIQ_33") (pintype "passive"))
    )
    (net (code "49") (name "/GPIO38") (class "Default")
      (node (ref "J2") (pin "12") (pinfunction "12_12") (pintype "passive"))
      (node (ref "U1") (pin "34") (pinfunction "GPIO38/FSPIWP/SUBSPIWP_34") (pintype "passive"))
    )
    (net (code "50") (name "/GPIO39") (class "Default")
      (node (ref "J2") (pin "11") (pinfunction "11_11") (pintype "passive"))
      (node (ref "U1") (pin "35") (pinfunction "MTCK/GPIO39/CLK_OUT3/SUBSPICS1_35") (pintype "passive"))
    )
    (net (code "51") (name "/GPIO40") (class "Default")
      (node (ref "J2") (pin "10") (pinfunction "10_10") (pintype "passive"))
      (node (ref "U1") (pin "36") (pinfunction "MTDO/GPIO40/CLK_OUT2_36") (pintype "passive"))
    )
    (net (code "52") (name "/GPIO41") (class "Default")
      (node (ref "J2") (pin "9") (pinfunction "9_9") (pintype "passive"))
      (node (ref "U1") (pin "37") (pinfunction "MTDI/GPIO41/CLK_OUT1_37") (pintype "passive"))
    )
    (net (code "53") (name "/GPIO42") (class "Default")
      (node (ref "J2") (pin "8") (pinfunction "8_8") (pintype "passive"))
      (node (ref "U1") (pin "38") (pinfunction "MTMS/GPIO42_38") (pintype "passive"))
    )
    (net (code "54") (name "/GPIO45") (class "Default")
      (node (ref "J2") (pin "5") (pinfunction "5_5") (pintype "passive"))
      (node (ref "U1") (pin "41") (pinfunction "GPIO45_41") (pintype "passive"))
    )
    (net (code "55") (name "/GPIO46") (class "Default")
      (node (ref "J2") (pin "4") (pinfunction "4_4") (pintype "passive"))
      (node (ref "U1") (pin "44") (pinfunction "GPIO46_44") (pintype "passive"))
    )
    (net (code "56") (name "/GPIO47") (class "Default")
      (node (ref "J2") (pin "23") (pinfunction "23_23") (pintype "passive"))
      (node (ref "U1") (pin "27") (pinfunction "GPIO47/SPICLK_P_DIFF/SUBSPICLK_P_DIFF_27") (pintype "passive"))
    )
    (net (code "57") (name "/GPIO48") (class "Default")
      (node (ref "J2") (pin "22") (pinfunction "22_22") (pintype "passive"))
      (node (ref "U1") (pin "30") (pinfunction "GPIO48/SPICLK_N_DIFF/SUBSPICLK_N_DIFF_30") (pintype "passive"))
    )
    (net (code "58") (name "/RTS_FTDI") (class "Default")
      (node (ref "Q1") (pin "2") (pinfunction "E_2") (pintype "passive"))
      (node (ref "R18") (pin "1") (pinfunction "1_1") (pintype "passive"))
      (node (ref "U2") (pin "19") (pinfunction "~{RTS}_19") (pintype "passive"))
    )
    (net (code "59") (name "/RXD_FTDI") (class "Default")
      (node (ref "R19") (pin "2") (pinfunction "2_2") (pintype "passive"))
      (node (ref "U2") (pin "1") (pinfunction "RXD_1") (pintype "passive"))
    )
    (net (code "60") (name "/TXD_FTDI") (class "Default")
      (node (ref "R20") (pin "2") (pinfunction "2_2") (pintype "passive"))
      (node (ref "U2") (pin "17") (pinfunction "TXD_17") (pintype "passive"))
    )
    (net (code "61") (name "/U0RXD") (class "Default")
      (node (ref "J2") (pin "6") (pinfunction "6_6") (pintype "passive"))
      (node (ref "R20") (pin "1") (pinfunction "1_1") (pintype "passive"))
      (node (ref "U1") (pin "40") (pinfunction "U0RXD/GPIO44/CLK_OUT2_40") (pintype "passive"))
    )
    (net (code "62") (name "/U0TXD") (class "Default")
      (node (ref "J2") (pin "7") (pinfunction "7_7") (pintype "passive"))
      (node (ref "R19") (pin "1") (pinfunction "1_1") (pintype "passive"))
      (node (ref "U1") (pin "39") (pinfunction "U0TXD/GPIO43/CLK_OUT1_39") (pintype "passive"))
    )
    (net (code "63") (name "/VBUS_SENSE") (class "Default")
      (node (ref "R10") (pin "2") (pinfunction "2_2") (pintype "passive"))
      (node (ref "R13") (pin "1") (pinfunction "1_1") (pintype "passive"))
      (node (ref "U2") (pin "16") (pinfunction "CBUS3_16") (pintype "passive"))
    )
    (net (code "64") (name "GND") (class "Default")
      (node (ref "C1") (pin "1") (pinfunction "1_1") (pintype "passive"))
      (node (ref "C10") (pin "1") (pinfunction "1_1") (pintype "passive"))
      (node (ref "C11") (pin "1") (pinfunction "2_1") (pintype "passive"))
      (node (ref "C12") (pin "1") (pinfunction "2_1") (pintype "passive"))
      (node (ref "C13") (pin "1") (pinfunction "2_1") (pintype "passive"))
      (node (ref "C14") (pin "1") (pinfunction "2_1") (pintype "passive"))
      (node (ref "C15") (pin "1") (pinfunction "1_1") (pintype "passive"))
      (node (ref "C16") (pin "1") (pinfunction "2_1") (pintype "passive"))
      (node (ref "C17") (pin "1") (pinfunction "1_1") (pintype "passive"))
      (node (ref "C2") (pin "1") (pinfunction "2_1") (pintype "passive"))
      (node (ref "C3") (pin "1") (pinfunction "1_1") (pintype "passive"))
      (node (ref "C4") (pin "1") (pinfunction "1_1") (pintype "passive"))
      (node (ref "C5") (pin "1") (pinfunction "1_1") (pintype "passive"))
      (node (ref "C6") (pin "1") (pinfunction "1_1") (pintype "passive"))
      (node (ref "C7") (pin "1") (pinfunction "1_1") (pintype "passive"))
      (node (ref "C8") (pin "1") (pinfunction "1_1") (pintype "passive"))
      (node (ref "C9") (pin "1") (pinfunction "1_1") (pintype "passive"))
      (node (ref "D1") (pin "1") (pinfunction "1_1") (pintype "passive"))
      (node (ref "D3") (pin "1") (pinfunction "1_1") (pintype "passive"))
      (node (ref "D4") (pin "1") (pinfunction "1_1") (pintype "passive"))
      (node (ref "D5") (pin "1") (pinfunction "1_1") (pintype "passive"))
      (node (ref "D6") (pin "1") (pinfunction "1_1") (pintype "passive"))
      (node (ref "D7") (pin "1") (pinfunction "1_1") (pintype "passive"))
      (node (ref "D8") (pin "1") (pinfunction "1_1") (pintype "passive"))
      (node (ref "J1") (pin "1") (pinfunction "1_1") (pintype "passive"))
      (node (ref "J1") (pin "23") (pinfunction "23_23") (pintype "passive"))
      (node (ref "J2") (pin "2") (pinfunction "2_2") (pintype "passive"))
      (node (ref "J2") (pin "24") (pinfunction "24_24") (pintype "passive"))
      (node (ref "J3") (pin "A1B12") (pinfunction "GND_A1B12_A1B12") (pintype "passive"))
      (node (ref "J3") (pin "B1A12") (pinfunction "GND_B1A12_B1A12") (pintype "passive"))
      (node (ref "J3") (pin "S1") (pinfunction "SHIELD_1_S1") (pintype "passive"))
      (node (ref "J3") (pin "S2") (pinfunction "SHIELD_2_S2") (pintype "passive"))
      (node (ref "J3") (pin "S3") (pinfunction "SHIELD_3_S3") (pintype "passive"))
      (node (ref "J3") (pin "S4") (pinfunction "SHIELD_4_S4") (pintype "passive"))
      (node (ref "J4") (pin "A1B12") (pinfunction "GND_A1B12_A1B12") (pintype "passive"))
      (node (ref "J4") (pin "B1A12") (pinfunction "GND_B1A12_B1A12") (pintype "passive"))
      (node (ref "J4") (pin "S1") (pinfunction "SHIELD_1_S1") (pintype "passive"))
      (node (ref "J4") (pin "S2") (pinfunction "SHIELD_2_S2") (pintype "passive"))
      (node (ref "J4") (pin "S3") (pinfunction "SHIELD_3_S3") (pintype "passive"))
      (node (ref "J4") (pin "S4") (pinfunction "SHIELD_4_S4") (pintype "passive"))
      (node (ref "R11") (pin "1") (pinfunction "1_1") (pintype "passive"))
      (node (ref "R12") (pin "1") (pinfunction "1_1") (pintype "passive"))
      (node (ref "R13") (pin "2") (pinfunction "2_2") (pintype "passive"))
      (node (ref "R14") (pin "1") (pinfunction "1_1") (pintype "passive"))
      (node (ref "R15") (pin "1") (pinfunction "1_1") (pintype "passive"))
      (node (ref "R9") (pin "1") (pinfunction "1_1") (pintype "passive"))
      (node (ref "SW1") (pin "3") (pinfunction "3_3") (pintype "passive"))
      (node (ref "SW1") (pin "4") (pinfunction "4_4") (pintype "passive"))
      (node (ref "SW2") (pin "3") (pinfunction "3_3") (pintype "passive"))
      (node (ref "SW2") (pin "4") (pinfunction "4_4") (pintype "passive"))
      (node (ref "U1") (pin "1") (pinfunction "GND_01_1") (pintype "passive"))
      (node (ref "U1") (pin "2") (pinfunction "GND_02_2") (pintype "passive"))
      (node (ref "U1") (pin "42") (pinfunction "GND_42") (pintype "passive"))
      (node (ref "U1") (pin "43") (pinfunction "GND_43") (pintype "passive"))
      (node (ref "U1") (pin "46") (pinfunction "GND_46_46") (pintype "passive"))
      (node (ref "U1") (pin "47") (pinfunction "GND_47_47") (pintype "passive"))
      (node (ref "U1") (pin "48") (pinfunction "GND_48_48") (pintype "passive"))
      (node (ref "U1") (pin "49") (pinfunction "GND_49_49") (pintype "passive"))
      (node (ref "U1") (pin "50") (pinfunction "GND_50_50") (pintype "passive"))
      (node (ref "U1") (pin "51") (pinfunction "GND_51_51") (pintype "passive"))
      (node (ref "U1") (pin "52") (pinfunction "GND_52_52") (pintype "passive"))
      (node (ref "U1") (pin "53") (pinfunction "GND_53_53") (pintype "passive"))
      (node (ref "U1") (pin "54") (pinfunction "GND_54_54") (pintype "passive"))
      (node (ref "U1") (pin "55") (pinfunction "GND_55_55") (pintype "passive"))
      (node (ref "U1") (pin "56") (pinfunction "GND_56_56") (pintype "passive"))
      (node (ref "U1") (pin "57") (pinfunction "GND_57_57") (pintype "passive"))
      (node (ref "U1") (pin "58") (pinfunction "GND_58_58") (pintype "passive"))
      (node (ref "U1") (pin "59") (pinfunction "GND_59_59") (pintype "passive"))
      (node (ref "U1") (pin "60") (pinfunction "GND_60_60") (pintype "passive"))
      (node (ref "U1") (pin "61") (pinfunction "GND_61_61") (pintype "passive"))
      (node (ref "U1") (pin "62") (pinfunction "GND_62_62") (pintype "passive"))
      (node (ref "U1") (pin "63") (pinfunction "GND_63_63") (pintype "passive"))
      (node (ref "U1") (pin "64") (pinfunction "GND_64_64") (pintype "passive"))
      (node (ref "U1") (pin "65") (pinfunction "GND_65_65") (pintype "passive"))
      (node (ref "U1") (pin "66") (pinfunction "GND_66_66") (pintype "passive"))
      (node (ref "U1") (pin "67") (pinfunction "GND_67_67") (pintype "passive"))
      (node (ref "U1") (pin "68") (pinfunction "GND_68_68") (pintype "passive"))
      (node (ref "U1") (pin "69") (pinfunction "GND_69_69") (pintype "passive"))
      (node (ref "U1") (pin "70") (pinfunction "GND_70_70") (pintype "passive"))
      (node (ref "U1") (pin "71") (pinfunction "GND_71_71") (pintype "passive"))
      (node (ref "U1") (pin "72") (pinfunction "GND_72_72") (pintype "passive"))
      (node (ref "U1") (pin "73") (pinfunction "GND_73_73") (pintype "passive"))
      (node (ref "U2") (pin "13") (pinfunction "GND_13") (pintype "passive"))
      (node (ref "U2") (pin "21") (pinfunction "GND_21") (pintype "passive"))
      (node (ref "U2") (pin "3") (pinfunction "GND_3") (pintype "passive"))
      (node (ref "U3") (pin "2") (pinfunction "GND_2") (pintype "power_in"))
      (node (ref "U3") (pin "4") (pinfunction "GND_4") (pintype "power_in"))
    )
    (net (code "65") (name "Net-(D1-Pad2)") (class "Default")
      (node (ref "D1") (pin "2") (pinfunction "2_2") (pintype "passive"))
      (node (ref "R3") (pin "1") (pinfunction "1_1") (pintype "passive"))
    )
    (net (code "66") (name "Net-(D2-Pad2)") (class "Default")
      (node (ref "D2") (pin "2") (pinfunction "2_2") (pintype "passive"))
      (node (ref "R4") (pin "1") (pinfunction "1_1") (pintype "passive"))
    )
    (net (code "67") (name "Net-(J3-CC1)") (class "Default")
      (node (ref "J3") (pin "A5") (pinfunction "CC1_A5") (pintype "passive"))
      (node (ref "R12") (pin "2") (pinfunction "2_2") (pintype "passive"))
    )
    (net (code "68") (name "Net-(J3-CC2)") (class "Default")
      (node (ref "J3") (pin "B5") (pinfunction "CC2_B5") (pintype "passive"))
      (node (ref "R11") (pin "2") (pinfunction "2_2") (pintype "passive"))
    )
    (net (code "69") (name "Net-(J4-CC1)") (class "Default")
      (node (ref "J4") (pin "A5") (pinfunction "CC1_A5") (pintype "passive"))
      (node (ref "R15") (pin "2") (pinfunction "2_2") (pintype "passive"))
    )
    (net (code "70") (name "Net-(J4-CC2)") (class "Default")
      (node (ref "J4") (pin "B5") (pinfunction "CC2_B5") (pintype "passive"))
      (node (ref "R14") (pin "2") (pinfunction "2_2") (pintype "passive"))
    )
    (net (code "71") (name "Net-(Q1-B)") (class "Default")
      (node (ref "Q1") (pin "1") (pinfunction "B_1") (pintype "passive"))
      (node (ref "R16") (pin "1") (pinfunction "1_1") (pintype "passive"))
    )
    (net (code "72") (name "Net-(Q2-B)") (class "Default")
      (node (ref "Q2") (pin "1") (pinfunction "B_1") (pintype "passive"))
      (node (ref "R18") (pin "2") (pinfunction "2_2") (pintype "passive"))
    )
    (net (code "73") (name "Net-(U2-CBUS0)") (class "Default")
      (node (ref "R9") (pin "2") (pinfunction "2_2") (pintype "passive"))
      (node (ref "U2") (pin "15") (pinfunction "CBUS0_15") (pintype "passive"))
    )
    (net (code "74") (name "unconnected-(J1-Pad24)") (class "Default")
      (node (ref "J1") (pin "24") (pinfunction "24_24") (pintype "passive+no_connect"))
    )
    (net (code "75") (name "unconnected-(J3-SBU1-PadA8)") (class "Default")
      (node (ref "J3") (pin "A8") (pinfunction "SBU1_A8") (pintype "passive+no_connect"))
    )
    (net (code "76") (name "unconnected-(J3-SBU2-PadB8)") (class "Default")
      (node (ref "J3") (pin "B8") (pinfunction "SBU2_B8") (pintype "passive+no_connect"))
    )
    (net (code "77") (name "unconnected-(J4-SBU1-PadA8)") (class "Default")
      (node (ref "J4") (pin "A8") (pinfunction "SBU1_A8") (pintype "passive+no_connect"))
    )
    (net (code "78") (name "unconnected-(J4-SBU2-PadB8)") (class "Default")
      (node (ref "J4") (pin "B8") (pinfunction "SBU2_B8") (pintype "passive+no_connect"))
    )
    (net (code "79") (name "unconnected-(U2-CBUS1-Pad14)") (class "Default")
      (node (ref "U2") (pin "14") (pinfunction "CBUS1_14") (pintype "passive+no_connect"))
    )
    (net (code "80") (name "unconnected-(U2-CBUS2-Pad7)") (class "Default")
      (node (ref "U2") (pin "7") (pinfunction "CBUS2_7") (pintype "passive+no_connect"))
    )
    (net (code "81") (name "unconnected-(U2-~{CTS}-Pad6)") (class "Default")
      (node (ref "U2") (pin "6") (pinfunction "~{CTS}_6") (pintype "passive+no_connect"))
    )
    (net (code "82") (name "unconnected-(U2-~{DCD}-Pad5)") (class "Default")
      (node (ref "U2") (pin "5") (pinfunction "~{DCD}_5") (pintype "passive+no_connect"))
    )
    (net (code "83") (name "unconnected-(U2-~{DSR}-Pad4)") (class "Default")
      (node (ref "U2") (pin "4") (pinfunction "~{DSR}_4") (pintype "passive+no_connect"))
    )
    (net (code "84") (name "unconnected-(U2-~{RI}-Pad2)") (class "Default")
      (node (ref "U2") (pin "2") (pinfunction "~{RI}_2") (pintype "passive"))
    )
  )
)
